# PowerStudent.net
KiCad netlist of a schematic drawn in Altium Designer
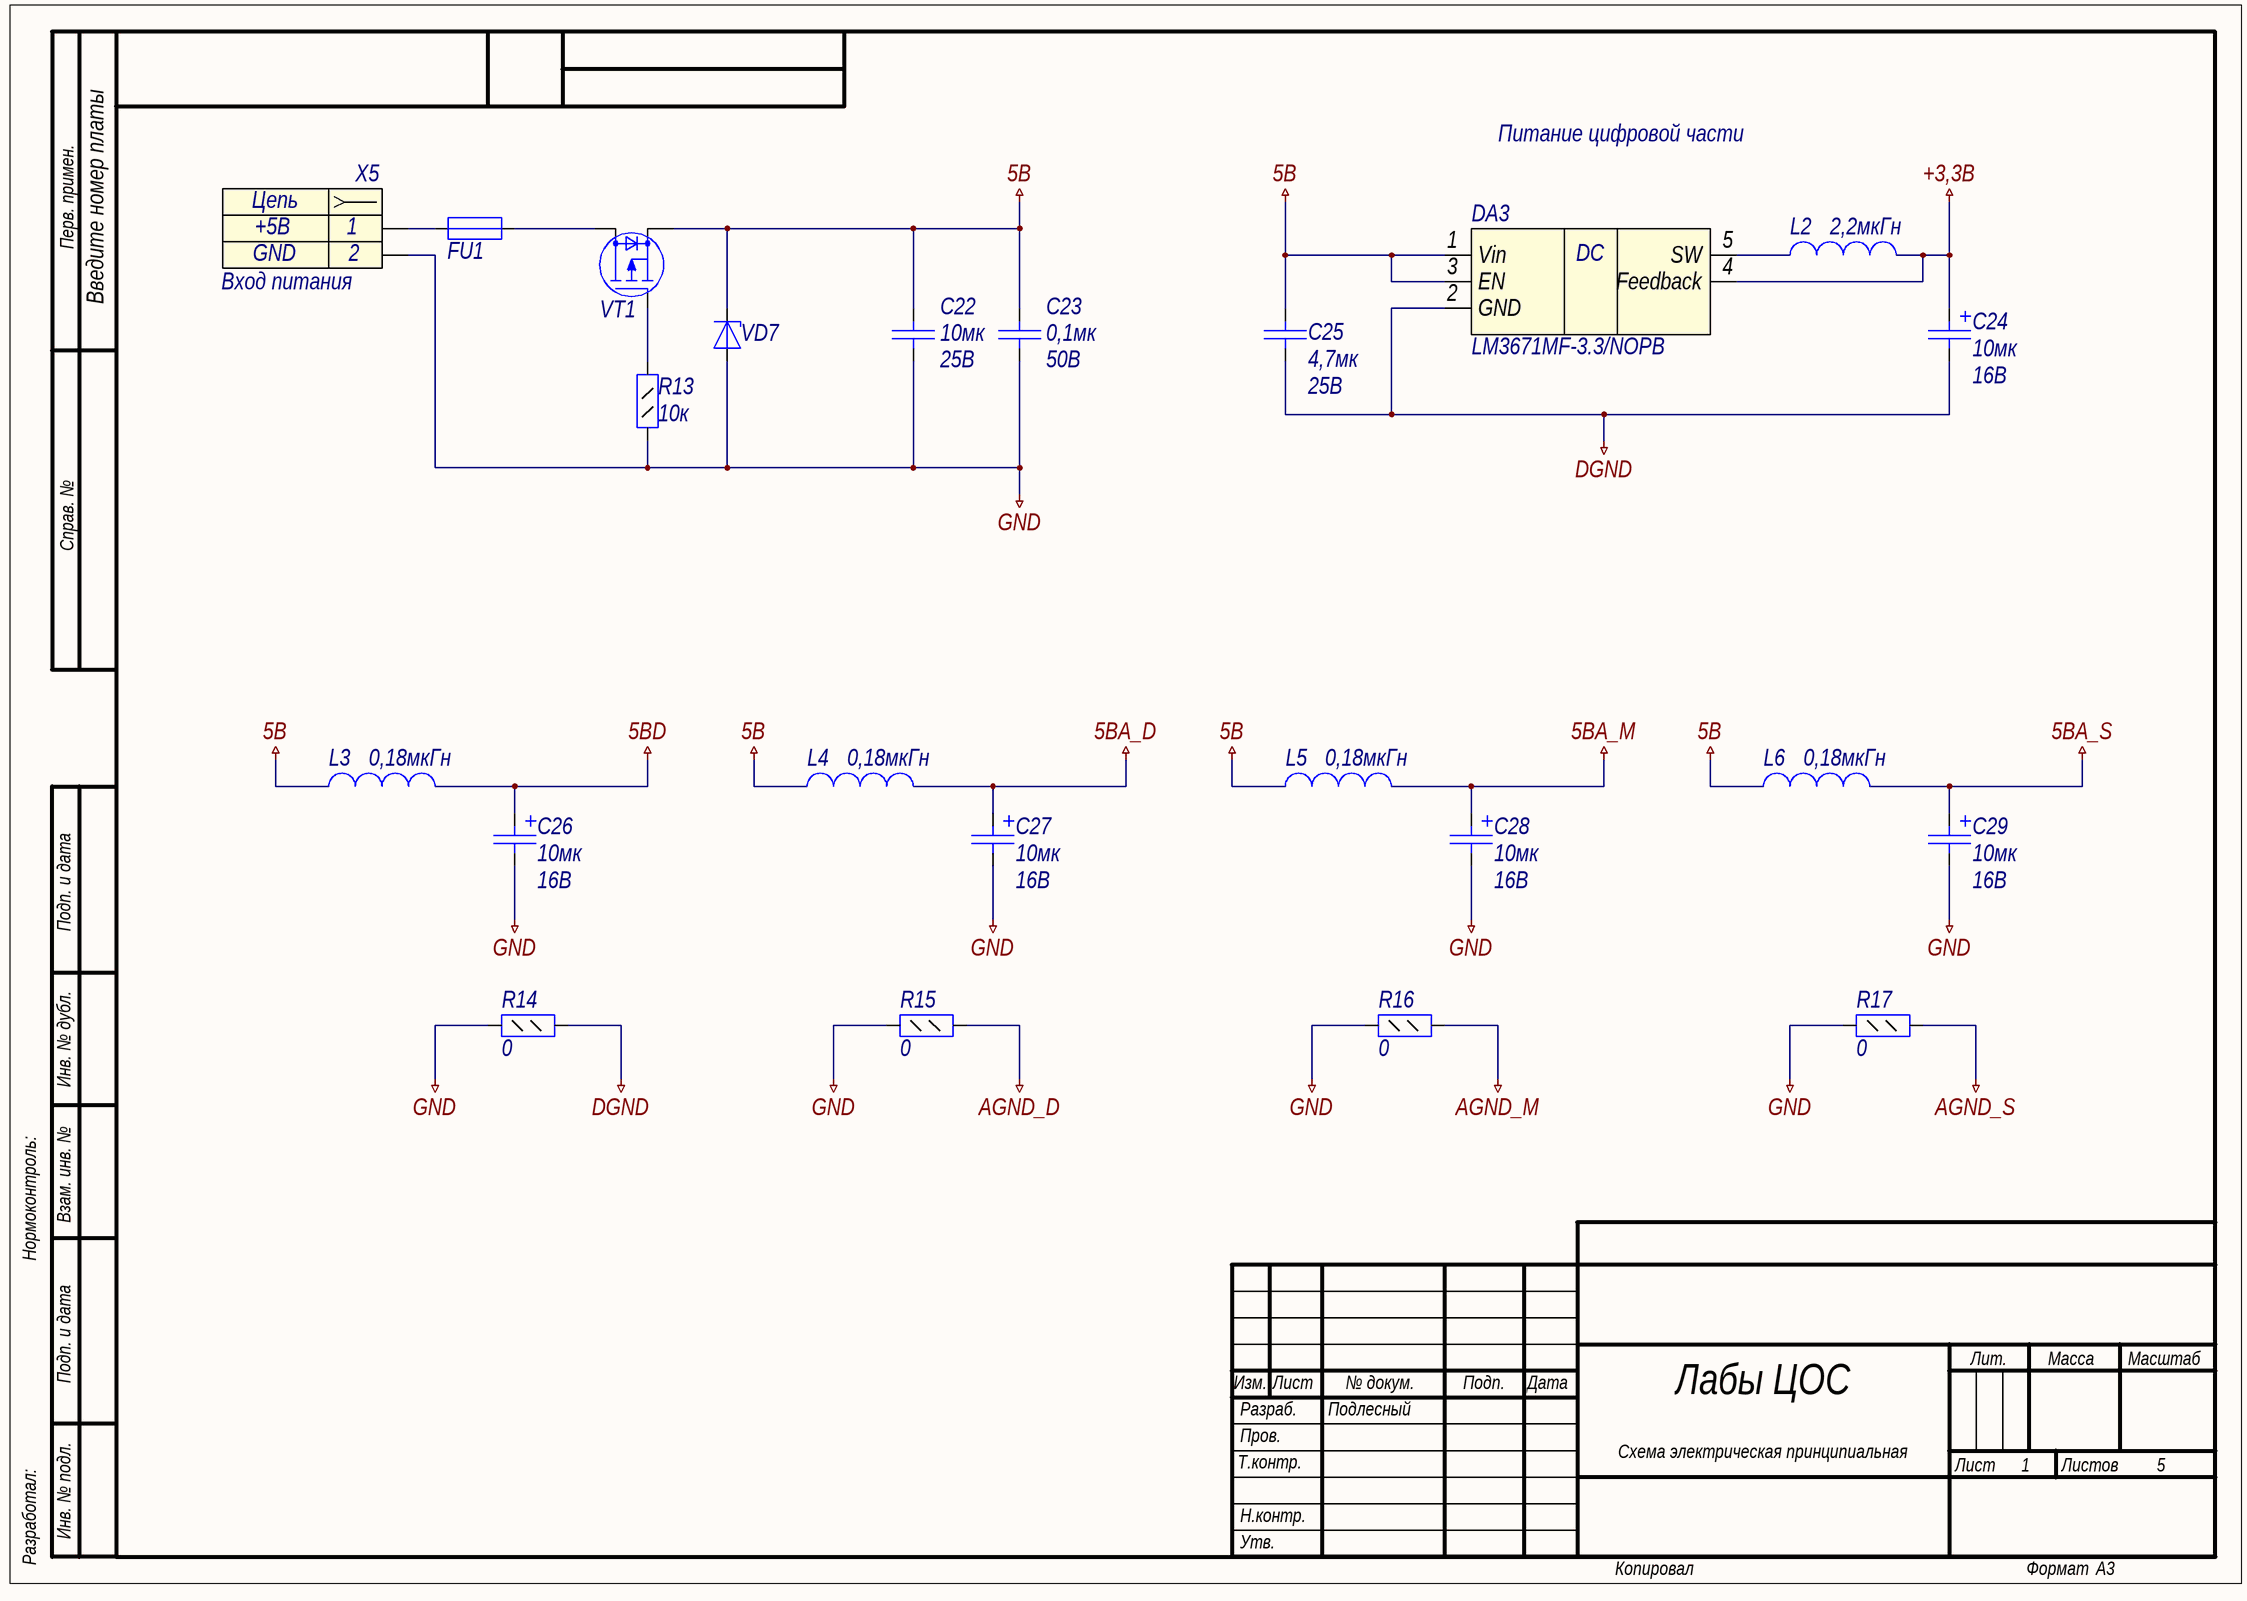
[diagram p0: PowerStudent.SchDoc]

(export (version "E")
  (design (tool "Eeschema 10.0.6"))
  (components
    (comp (ref "C22")
      (value "10мк")
      (footprint "C1206")
      (description "Конденсатор")
      (fields
        (field (name "VOLTAGE") "25В")
        (field (name "PART NUMBER") "GRM31CR71E106KA12L*")
        (field (name "Comment") "Capacitor")
      )
      (libsource (lib "MOP44") (part "Capacitor"))
    )
    (comp (ref "C23")
      (value "0,1мк")
      (footprint "C0805")
      (description "Конденсатор")
      (fields
        (field (name "VOLTAGE") "50В")
        (field (name "PART NUMBER") "GRM21BR71H104KA01L ")
        (field (name "Comment") "Capacitor")
      )
      (libsource (lib "MOP44") (part "Capacitor"))
    )
    (comp (ref "C24")
      (value "10мк")
      (footprint "TANTAL CASE A")
      (description "Конденсатор полярный")
      (fields
        (field (name "VOLTAGE") "16В")
        (field (name "PART NUMBER") "293D106X9016A2TE3")
        (field (name "Comment") "Capacitor_pol")
      )
      (libsource (lib "MOP44") (part "Capacitor_pol"))
    )
    (comp (ref "C25")
      (value "4,7мк")
      (footprint "C0805")
      (description "Конденсатор")
      (fields
        (field (name "VOLTAGE") "25B")
        (field (name "PART NUMBER") "GRM21BR61E475KA12L")
        (field (name "Comment") "Capacitor")
      )
      (libsource (lib "MOP44") (part "Capacitor"))
    )
    (comp (ref "C26")
      (value "10мк")
      (footprint "TANTAL CASE A")
      (description "Конденсатор полярный")
      (fields
        (field (name "VOLTAGE") "16В")
        (field (name "PART NUMBER") "293D106X9016A2TE3")
        (field (name "Comment") "Capacitor_pol")
      )
      (libsource (lib "MOP44") (part "Capacitor_pol"))
    )
    (comp (ref "C27")
      (value "10мк")
      (footprint "TANTAL CASE A")
      (description "Конденсатор полярный")
      (fields
        (field (name "VOLTAGE") "16В")
        (field (name "PART NUMBER") "293D106X9016A2TE3")
        (field (name "Comment") "Capacitor_pol")
      )
      (libsource (lib "MOP44") (part "Capacitor_pol"))
    )
    (comp (ref "C28")
      (value "10мк")
      (footprint "TANTAL CASE A")
      (description "Конденсатор полярный")
      (fields
        (field (name "VOLTAGE") "16В")
        (field (name "PART NUMBER") "293D106X9016A2TE3")
        (field (name "Comment") "Capacitor_pol")
      )
      (libsource (lib "MOP44") (part "Capacitor_pol"))
    )
    (comp (ref "C29")
      (value "10мк")
      (footprint "TANTAL CASE A")
      (description "Конденсатор полярный")
      (fields
        (field (name "VOLTAGE") "16В")
        (field (name "PART NUMBER") "293D106X9016A2TE3")
        (field (name "Comment") "Capacitor_pol")
      )
      (libsource (lib "MOP44") (part "Capacitor_pol"))
    )
    (comp (ref "DA3")
      (value "LM3671MF")
      (footprint "SOT23-5")
      (description "Step-Down DC-DC Converter")
      (fields
        (field (name "PART NUMBER") "LM3671MF-3.3/NOPB")
        (field (name "MANUFACTURER") "Texas Instruments")
      )
      (libsource (lib "MOP44") (part "LM3671MF"))
    )
    (comp (ref "FU1")
      (value "Fuse")
      (footprint "FUSE812")
      (description "Предохранитель")
      (fields (field (name "PART NUMBER") "MF-MSMF075"))
      (libsource (lib "MOP44") (part "Fuse"))
    )
    (comp (ref "L2")
      (value "2,2мкГн")
      (footprint "SDR0604")
      (description "EMI Suppression Filter")
      (fields (field (name "PART NUMBER") "SDR0604-2R2ML") (field (name "Comment") "Inductor"))
      (libsource (lib "MOP44") (part "Inductor"))
    )
    (comp (ref "L3")
      (value "0,18мкГн")
      (footprint "L0805")
      (description "EMI Suppression Filter")
      (fields (field (name "PART NUMBER") "CM201212-R18KL") (field (name "Comment") "Inductor"))
      (libsource (lib "MOP44") (part "Inductor"))
    )
    (comp (ref "L4")
      (value "0,18мкГн")
      (footprint "L0805")
      (description "EMI Suppression Filter")
      (fields (field (name "PART NUMBER") "CM201212-R18KL") (field (name "Comment") "Inductor"))
      (libsource (lib "MOP44") (part "Inductor"))
    )
    (comp (ref "L5")
      (value "0,18мкГн")
      (footprint "L0805")
      (description "EMI Suppression Filter")
      (fields (field (name "PART NUMBER") "CM201212-R18KL") (field (name "Comment") "Inductor"))
      (libsource (lib "MOP44") (part "Inductor"))
    )
    (comp (ref "L6")
      (value "0,18мкГн")
      (footprint "L0805")
      (description "EMI Suppression Filter")
      (fields (field (name "PART NUMBER") "CM201212-R18KL") (field (name "Comment") "Inductor"))
      (libsource (lib "MOP44") (part "Inductor"))
    )
    (comp (ref "R13")
      (value "10к")
      (footprint "R0805")
      (description "Резистор")
      (fields (field (name "PART NUMBER") "RC0805FR-0710KL") (field (name "POWER") "0,125Вт"))
      (libsource (lib "") (part "Resistor_0,125Вт_1"))
    )
    (comp (ref "R14")
      (value "0")
      (footprint "R0805")
      (description "Резистор")
      (fields (field (name "PART NUMBER") "RC0805FR-070RL") (field (name "POWER") "0,125Вт"))
      (libsource (lib "MOP44") (part "Resistor_0,125Вт"))
    )
    (comp (ref "R15")
      (value "0")
      (footprint "R0805")
      (description "Резистор")
      (fields (field (name "PART NUMBER") "RC0805FR-070RL") (field (name "POWER") "0,125Вт"))
      (libsource (lib "MOP44") (part "Resistor_0,125Вт"))
    )
    (comp (ref "R16")
      (value "0")
      (footprint "R0805")
      (description "Резистор")
      (fields (field (name "PART NUMBER") "RC0805FR-070RL") (field (name "POWER") "0,125Вт"))
      (libsource (lib "MOP44") (part "Resistor_0,125Вт"))
    )
    (comp (ref "R17")
      (value "0")
      (footprint "R0805")
      (description "Резистор")
      (fields (field (name "PART NUMBER") "RC0805FR-070RL") (field (name "POWER") "0,125Вт"))
      (libsource (lib "MOP44") (part "Resistor_0,125Вт"))
    )
    (comp (ref "VD7")
      (value "DiodeZener")
      (footprint "SMA")
      (description "Cтабилитрон (лавинный выпрямительный диод) односторонний")
      (fields (field (name "PART NUMBER") "SMAJ5.0A-TR"))
      (libsource (lib "MOP44") (part "DiodeZener"))
    )
    (comp (ref "VT1")
      (value "P-MOSFET")
      (footprint "SOT23-3")
      (description "N-MOSFET")
      (fields (field (name "PART NUMBER") "IRLML6401TRPBF"))
      (libsource (lib "MOP44") (part "P-MOSFET"))
    )
    (comp (ref "X5")
      (value "Вход питания")
      (footprint "DS-210")
      (description "Разъем - 2 конт. розетка")
      (fields (field (name "PART NUMBER") "DS-210B(PBT)(NB)"))
      (libsource (lib "MOP44") (part "Header_2_sct"))
    )
  )
  (nets
    (net (code "1") (name "+3,3В") (class "Default")
      (node (ref "C24") (pin "1") (pinfunction "1_1") (pintype "passive"))
      (node (ref "DA3") (pin "4") (pinfunction "Feedback_4") (pintype "power_in"))
      (node (ref "L2") (pin "2") (pinfunction "2_2") (pintype "passive"))
    )
    (net (code "2") (name "5B") (class "Default")
      (node (ref "C22") (pin "2") (pinfunction "2_2") (pintype "passive"))
      (node (ref "C23") (pin "2") (pinfunction "2_2") (pintype "passive"))
      (node (ref "C25") (pin "2") (pinfunction "2_2") (pintype "passive"))
      (node (ref "DA3") (pin "1") (pinfunction "Vin_1") (pintype "power_in"))
      (node (ref "DA3") (pin "3") (pinfunction "EN_3") (pintype "power_in"))
      (node (ref "L3") (pin "1") (pinfunction "1_1") (pintype "passive"))
      (node (ref "L4") (pin "1") (pinfunction "1_1") (pintype "passive"))
      (node (ref "L5") (pin "1") (pinfunction "1_1") (pintype "passive"))
      (node (ref "L6") (pin "1") (pinfunction "1_1") (pintype "passive"))
      (node (ref "VD7") (pin "1") (pinfunction "K_1") (pintype "passive"))
      (node (ref "VT1") (pin "2") (pinfunction "S_2") (pintype "passive"))
    )
    (net (code "3") (name "5BA_D") (class "Default")
      (node (ref "C27") (pin "1") (pinfunction "1_1") (pintype "passive"))
      (node (ref "L4") (pin "2") (pinfunction "2_2") (pintype "passive"))
    )
    (net (code "4") (name "5BA_M") (class "Default")
      (node (ref "C28") (pin "1") (pinfunction "1_1") (pintype "passive"))
      (node (ref "L5") (pin "2") (pinfunction "2_2") (pintype "passive"))
    )
    (net (code "5") (name "5BA_S") (class "Default")
      (node (ref "C29") (pin "1") (pinfunction "1_1") (pintype "passive"))
      (node (ref "L6") (pin "2") (pinfunction "2_2") (pintype "passive"))
    )
    (net (code "6") (name "5BD") (class "Default")
      (node (ref "C26") (pin "1") (pinfunction "1_1") (pintype "passive"))
      (node (ref "L3") (pin "2") (pinfunction "2_2") (pintype "passive"))
    )
    (net (code "7") (name "AGND_D") (class "Default")
      (node (ref "R15") (pin "2") (pinfunction "2_2") (pintype "passive"))
    )
    (net (code "8") (name "AGND_M") (class "Default")
      (node (ref "R16") (pin "2") (pinfunction "2_2") (pintype "passive"))
    )
    (net (code "9") (name "AGND_S") (class "Default")
      (node (ref "R17") (pin "2") (pinfunction "2_2") (pintype "passive"))
    )
    (net (code "10") (name "DGND") (class "Default")
      (node (ref "C24") (pin "2") (pinfunction "2_2") (pintype "passive"))
      (node (ref "C25") (pin "1") (pinfunction "1_1") (pintype "passive"))
      (node (ref "DA3") (pin "2") (pinfunction "GND_2") (pintype "power_in"))
      (node (ref "R14") (pin "2") (pinfunction "2_2") (pintype "passive"))
    )
    (net (code "11") (name "GND") (class "Default")
      (node (ref "C22") (pin "1") (pinfunction "1_1") (pintype "passive"))
      (node (ref "C23") (pin "1") (pinfunction "1_1") (pintype "passive"))
      (node (ref "C26") (pin "2") (pinfunction "2_2") (pintype "passive"))
      (node (ref "C27") (pin "2") (pinfunction "2_2") (pintype "passive"))
      (node (ref "C28") (pin "2") (pinfunction "2_2") (pintype "passive"))
      (node (ref "C29") (pin "2") (pinfunction "2_2") (pintype "passive"))
      (node (ref "R13") (pin "1") (pinfunction "1_1") (pintype "passive"))
      (node (ref "R14") (pin "1") (pinfunction "1_1") (pintype "passive"))
      (node (ref "R15") (pin "1") (pinfunction "1_1") (pintype "passive"))
      (node (ref "R16") (pin "1") (pinfunction "1_1") (pintype "passive"))
      (node (ref "R17") (pin "1") (pinfunction "1_1") (pintype "passive"))
      (node (ref "VD7") (pin "2") (pinfunction "A_2") (pintype "passive"))
      (node (ref "X5") (pin "2") (pinfunction "2_2") (pintype "passive"))
    )
    (net (code "12") (name "Net-(DA3-SW)") (class "Default")
      (node (ref "DA3") (pin "5") (pinfunction "SW_5") (pintype "power_in"))
      (node (ref "L2") (pin "1") (pinfunction "1_1") (pintype "passive"))
    )
    (net (code "13") (name "Net-(FU1-Pad1)") (class "Default")
      (node (ref "FU1") (pin "1") (pinfunction "1_1") (pintype "passive"))
      (node (ref "X5") (pin "1") (pinfunction "1_1") (pintype "passive"))
    )
    (net (code "14") (name "Net-(VT1-D)") (class "Default")
      (node (ref "FU1") (pin "2") (pinfunction "2_2") (pintype "passive"))
      (node (ref "VT1") (pin "3") (pinfunction "D_3") (pintype "passive"))
    )
    (net (code "15") (name "Net-(VT1-G)") (class "Default")
      (node (ref "R13") (pin "2") (pinfunction "2_2") (pintype "passive"))
      (node (ref "VT1") (pin "1") (pinfunction "G_1") (pintype "passive"))
    )
  )
)
